# Connector.net
KiCad netlist of a schematic drawn in Altium Designer
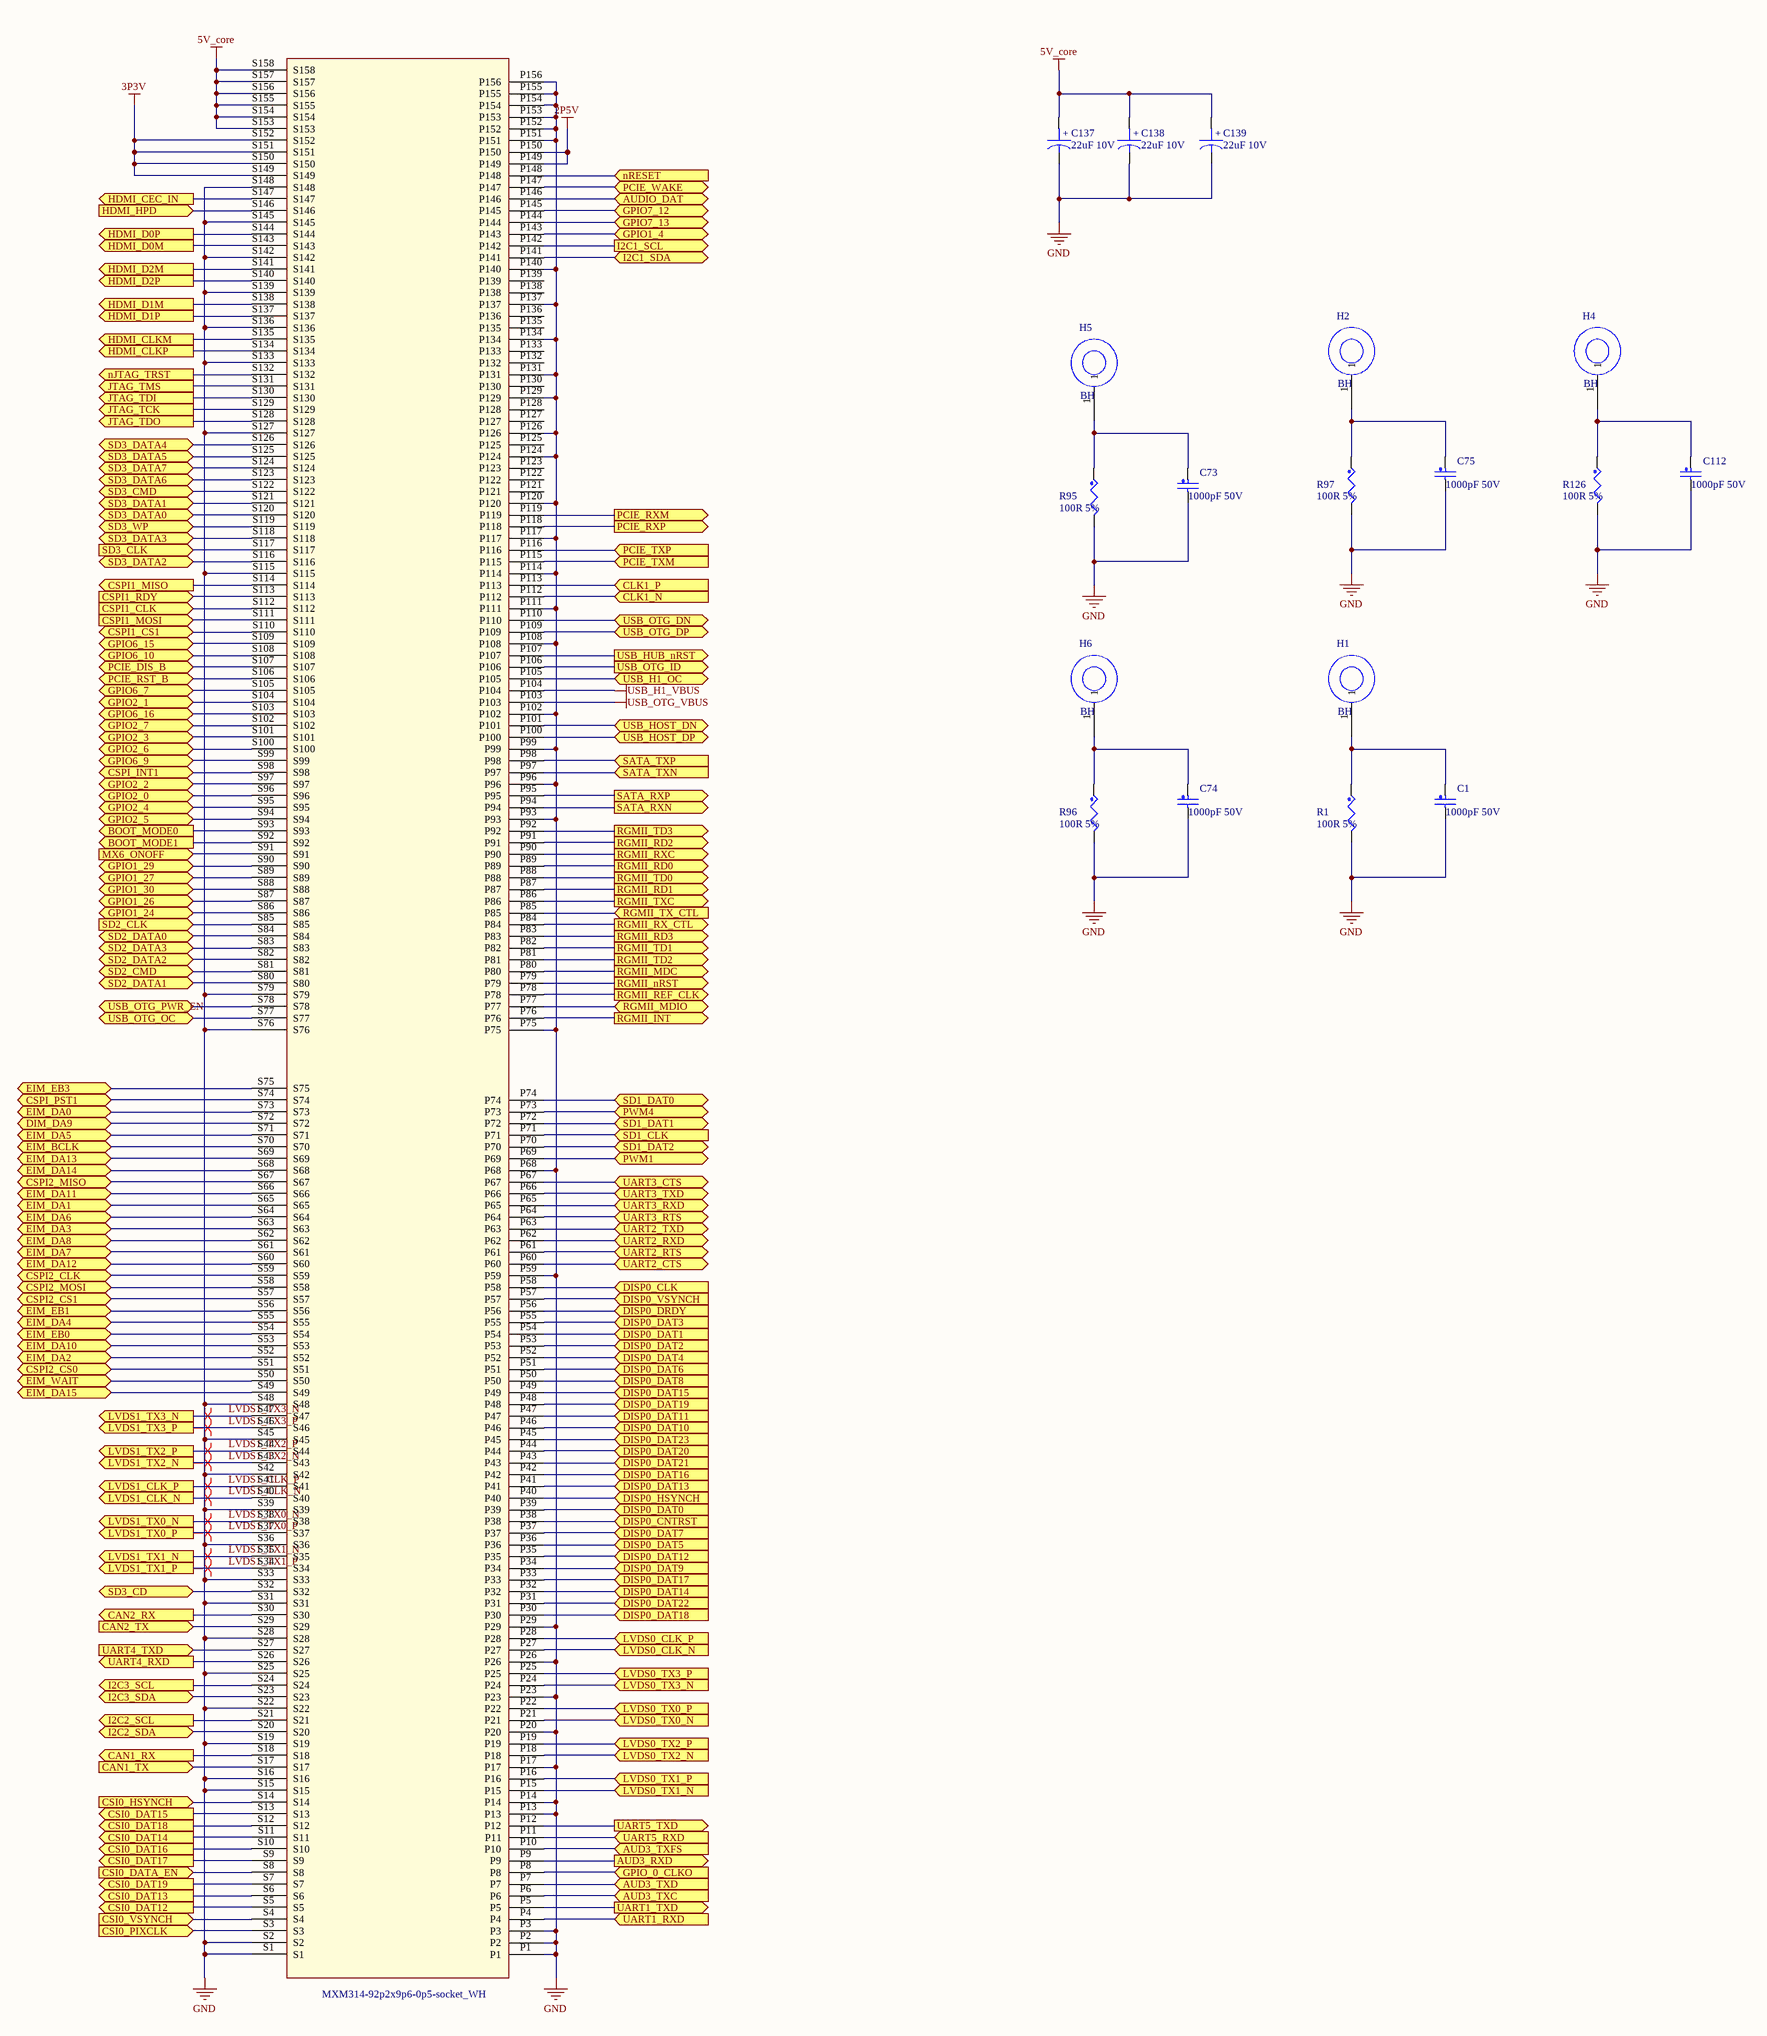
[diagram p0: Connector.SchDoc]

(export (version "E")
  (design (tool "Eeschema 10.0.6"))
  (components
    (comp (ref "C1")
      (value "1000pF 50V")
      (footprint "SC0603")
      (libsource (lib "MY-I.MX6-SCH_Library") (part "CAP_NP"))
    )
    (comp (ref "C73")
      (value "1000pF 50V")
      (footprint "SC0603")
      (libsource (lib "MY-I.MX6-SCH_Library") (part "CAP_NP"))
    )
    (comp (ref "C74")
      (value "1000pF 50V")
      (footprint "SC0603")
      (libsource (lib "MY-I.MX6-SCH_Library") (part "CAP_NP"))
    )
    (comp (ref "C75")
      (value "1000pF 50V")
      (footprint "SC0603")
      (libsource (lib "MY-I.MX6-SCH_Library") (part "CAP_NP"))
    )
    (comp (ref "C112")
      (value "1000pF 50V")
      (footprint "SC0603")
      (libsource (lib "MY-I.MX6-SCH_Library") (part "CAP_NP"))
    )
    (comp (ref "C137")
      (value "22uF 10V")
      (footprint "SC0805")
      (libsource (lib "MY-I.MX6-SCH_Library") (part "CAP POL"))
    )
    (comp (ref "C138")
      (value "22uF 10V")
      (footprint "SC0805")
      (libsource (lib "MY-I.MX6-SCH_Library") (part "CAP POL"))
    )
    (comp (ref "C139")
      (value "22uF 10V")
      (footprint "SC0805")
      (libsource (lib "MY-I.MX6-SCH_Library") (part "CAP POL"))
    )
    (comp (ref "H1") (value "BH") (footprint "H30") (libsource (lib "MY-I.MX6-SCH_Library") (part "BH")))
    (comp (ref "H2") (value "BH") (footprint "H30") (libsource (lib "MY-I.MX6-SCH_Library") (part "BH")))
    (comp (ref "H4") (value "BH") (footprint "H30") (libsource (lib "MY-I.MX6-SCH_Library") (part "BH")))
    (comp (ref "H5") (value "BH") (footprint "H30") (libsource (lib "MY-I.MX6-SCH_Library") (part "BH")))
    (comp (ref "H6") (value "BH") (footprint "H30") (libsource (lib "MY-I.MX6-SCH_Library") (part "BH")))
    (comp (ref "MXM314-92p2x9p6-0p5-socket_WH")
      (value "MXM314-92p2x9p6-0p5-socket_WH")
      (footprint "MXM314-92P2X9P6-0P5-SOCKET_WH")
      (libsource (lib "MY-I.MX6-SCH_Library") (part "MXM314"))
    )
    (comp (ref "R1")
      (value "100R 5%")
      (footprint "SR0603")
      (libsource (lib "MY-I.MX6-SCH_Library") (part "RES"))
    )
    (comp (ref "R95")
      (value "100R 5%")
      (footprint "SR0603")
      (libsource (lib "MY-I.MX6-SCH_Library") (part "RES"))
    )
    (comp (ref "R96")
      (value "100R 5%")
      (footprint "SR0603")
      (libsource (lib "MY-I.MX6-SCH_Library") (part "RES"))
    )
    (comp (ref "R97")
      (value "100R 5%")
      (footprint "SR0603")
      (libsource (lib "MY-I.MX6-SCH_Library") (part "RES"))
    )
    (comp (ref "R126")
      (value "100R 5%")
      (footprint "SR0603")
      (libsource (lib "MY-I.MX6-SCH_Library") (part "RES"))
    )
  )
  (nets
    (net (code "1") (name "/AUD3_RXD") (class "Default")
      (node (ref "MXM314-92p2x9p6-0p5-socket_WH") (pin "P9") (pinfunction "P9_P9") (pintype "passive"))
    )
    (net (code "2") (name "/AUD3_TXC") (class "Default")
      (node (ref "MXM314-92p2x9p6-0p5-socket_WH") (pin "P6") (pinfunction "P6_P6") (pintype "passive"))
    )
    (net (code "3") (name "/AUD3_TXD") (class "Default")
      (node (ref "MXM314-92p2x9p6-0p5-socket_WH") (pin "P7") (pinfunction "P7_P7") (pintype "passive"))
    )
    (net (code "4") (name "/AUD3_TXFS") (class "Default")
      (node (ref "MXM314-92p2x9p6-0p5-socket_WH") (pin "P10") (pinfunction "P10_P10") (pintype "passive"))
    )
    (net (code "5") (name "/AUDIO_DAT") (class "Default")
      (node (ref "MXM314-92p2x9p6-0p5-socket_WH") (pin "P146") (pinfunction "P146_P146") (pintype "passive"))
    )
    (net (code "6") (name "/BOOT_MODE0") (class "Default")
      (node (ref "MXM314-92p2x9p6-0p5-socket_WH") (pin "S93") (pinfunction "S93_S93") (pintype "passive"))
    )
    (net (code "7") (name "/BOOT_MODE1") (class "Default")
      (node (ref "MXM314-92p2x9p6-0p5-socket_WH") (pin "S92") (pinfunction "S92_S92") (pintype "passive"))
    )
    (net (code "8") (name "/CAN1_RX") (class "Default")
      (node (ref "MXM314-92p2x9p6-0p5-socket_WH") (pin "S18") (pinfunction "S18_S18") (pintype "passive"))
    )
    (net (code "9") (name "/CAN1_TX") (class "Default")
      (node (ref "MXM314-92p2x9p6-0p5-socket_WH") (pin "S17") (pinfunction "S17_S17") (pintype "passive"))
    )
    (net (code "10") (name "/CAN2_RX") (class "Default")
      (node (ref "MXM314-92p2x9p6-0p5-socket_WH") (pin "S30") (pinfunction "S30_S30") (pintype "passive"))
    )
    (net (code "11") (name "/CAN2_TX") (class "Default")
      (node (ref "MXM314-92p2x9p6-0p5-socket_WH") (pin "S29") (pinfunction "S29_S29") (pintype "passive"))
    )
    (net (code "12") (name "/CLK1_N") (class "Default")
      (node (ref "MXM314-92p2x9p6-0p5-socket_WH") (pin "P112") (pinfunction "P112_P112") (pintype "passive"))
    )
    (net (code "13") (name "/CLK1_P") (class "Default")
      (node (ref "MXM314-92p2x9p6-0p5-socket_WH") (pin "P113") (pinfunction "P113_P113") (pintype "passive"))
    )
    (net (code "14") (name "/CSI0_DAT12") (class "Default")
      (node (ref "MXM314-92p2x9p6-0p5-socket_WH") (pin "S5") (pinfunction "S5_S5") (pintype "passive"))
    )
    (net (code "15") (name "/CSI0_DAT13") (class "Default")
      (node (ref "MXM314-92p2x9p6-0p5-socket_WH") (pin "S6") (pinfunction "S6_S6") (pintype "passive"))
    )
    (net (code "16") (name "/CSI0_DAT14") (class "Default")
      (node (ref "MXM314-92p2x9p6-0p5-socket_WH") (pin "S11") (pinfunction "S11_S11") (pintype "passive"))
    )
    (net (code "17") (name "/CSI0_DAT15") (class "Default")
      (node (ref "MXM314-92p2x9p6-0p5-socket_WH") (pin "S13") (pinfunction "S13_S13") (pintype "passive"))
    )
    (net (code "18") (name "/CSI0_DAT16") (class "Default")
      (node (ref "MXM314-92p2x9p6-0p5-socket_WH") (pin "S10") (pinfunction "S10_S10") (pintype "passive"))
    )
    (net (code "19") (name "/CSI0_DAT17") (class "Default")
      (node (ref "MXM314-92p2x9p6-0p5-socket_WH") (pin "S9") (pinfunction "S9_S9") (pintype "passive"))
    )
    (net (code "20") (name "/CSI0_DAT18") (class "Default")
      (node (ref "MXM314-92p2x9p6-0p5-socket_WH") (pin "S12") (pinfunction "S12_S12") (pintype "passive"))
    )
    (net (code "21") (name "/CSI0_DAT19") (class "Default")
      (node (ref "MXM314-92p2x9p6-0p5-socket_WH") (pin "S7") (pinfunction "S7_S7") (pintype "passive"))
    )
    (net (code "22") (name "/CSI0_DATA_EN") (class "Default")
      (node (ref "MXM314-92p2x9p6-0p5-socket_WH") (pin "S8") (pinfunction "S8_S8") (pintype "passive"))
    )
    (net (code "23") (name "/CSI0_HSYNCH") (class "Default")
      (node (ref "MXM314-92p2x9p6-0p5-socket_WH") (pin "S14") (pinfunction "S14_S14") (pintype "passive"))
    )
    (net (code "24") (name "/CSI0_PIXCLK") (class "Default")
      (node (ref "MXM314-92p2x9p6-0p5-socket_WH") (pin "S3") (pinfunction "S3_S3") (pintype "passive"))
    )
    (net (code "25") (name "/CSI0_VSYNCH") (class "Default")
      (node (ref "MXM314-92p2x9p6-0p5-socket_WH") (pin "S4") (pinfunction "S4_S4") (pintype "passive"))
    )
    (net (code "26") (name "/CSPI1_CLK") (class "Default")
      (node (ref "MXM314-92p2x9p6-0p5-socket_WH") (pin "S112") (pinfunction "S112_S112") (pintype "passive"))
    )
    (net (code "27") (name "/CSPI1_CS1") (class "Default")
      (node (ref "MXM314-92p2x9p6-0p5-socket_WH") (pin "S110") (pinfunction "S110_S110") (pintype "passive"))
    )
    (net (code "28") (name "/CSPI1_MISO") (class "Default")
      (node (ref "MXM314-92p2x9p6-0p5-socket_WH") (pin "S114") (pinfunction "S114_S114") (pintype "passive"))
    )
    (net (code "29") (name "/CSPI1_MOSI") (class "Default")
      (node (ref "MXM314-92p2x9p6-0p5-socket_WH") (pin "S111") (pinfunction "S111_S111") (pintype "passive"))
    )
    (net (code "30") (name "/CSPI1_RDY") (class "Default")
      (node (ref "MXM314-92p2x9p6-0p5-socket_WH") (pin "S113") (pinfunction "S113_S113") (pintype "passive"))
    )
    (net (code "31") (name "/CSPI2_CLK") (class "Default")
      (node (ref "MXM314-92p2x9p6-0p5-socket_WH") (pin "S59") (pinfunction "S59_S59") (pintype "passive"))
    )
    (net (code "32") (name "/CSPI2_CS0") (class "Default")
      (node (ref "MXM314-92p2x9p6-0p5-socket_WH") (pin "S51") (pinfunction "S51_S51") (pintype "passive"))
    )
    (net (code "33") (name "/CSPI2_CS1") (class "Default")
      (node (ref "MXM314-92p2x9p6-0p5-socket_WH") (pin "S57") (pinfunction "S57_S57") (pintype "passive"))
    )
    (net (code "34") (name "/CSPI2_MISO") (class "Default")
      (node (ref "MXM314-92p2x9p6-0p5-socket_WH") (pin "S67") (pinfunction "S67_S67") (pintype "passive"))
    )
    (net (code "35") (name "/CSPI2_MOSI") (class "Default")
      (node (ref "MXM314-92p2x9p6-0p5-socket_WH") (pin "S58") (pinfunction "S58_S58") (pintype "passive"))
    )
    (net (code "36") (name "/CSPI_INT1") (class "Default")
      (node (ref "MXM314-92p2x9p6-0p5-socket_WH") (pin "S98") (pinfunction "S98_S98") (pintype "passive"))
    )
    (net (code "37") (name "/CSPI_PST1") (class "Default")
      (node (ref "MXM314-92p2x9p6-0p5-socket_WH") (pin "S74") (pinfunction "S74_S74") (pintype "passive"))
    )
    (net (code "38") (name "/DIM_DA9") (class "Default")
      (node (ref "MXM314-92p2x9p6-0p5-socket_WH") (pin "S72") (pinfunction "S72_S72") (pintype "passive"))
    )
    (net (code "39") (name "/DISP0_CLK") (class "Default")
      (node (ref "MXM314-92p2x9p6-0p5-socket_WH") (pin "P58") (pinfunction "P58_P58") (pintype "passive"))
    )
    (net (code "40") (name "/DISP0_CNTRST") (class "Default")
      (node (ref "MXM314-92p2x9p6-0p5-socket_WH") (pin "P38") (pinfunction "P38_P38") (pintype "passive"))
    )
    (net (code "41") (name "/DISP0_DAT0") (class "Default")
      (node (ref "MXM314-92p2x9p6-0p5-socket_WH") (pin "P39") (pinfunction "P39_P39") (pintype "passive"))
    )
    (net (code "42") (name "/DISP0_DAT1") (class "Default")
      (node (ref "MXM314-92p2x9p6-0p5-socket_WH") (pin "P54") (pinfunction "P54_P54") (pintype "passive"))
    )
    (net (code "43") (name "/DISP0_DAT2") (class "Default")
      (node (ref "MXM314-92p2x9p6-0p5-socket_WH") (pin "P53") (pinfunction "P53_P53") (pintype "passive"))
    )
    (net (code "44") (name "/DISP0_DAT3") (class "Default")
      (node (ref "MXM314-92p2x9p6-0p5-socket_WH") (pin "P55") (pinfunction "P55_P55") (pintype "passive"))
    )
    (net (code "45") (name "/DISP0_DAT4") (class "Default")
      (node (ref "MXM314-92p2x9p6-0p5-socket_WH") (pin "P52") (pinfunction "P52_P52") (pintype "passive"))
    )
    (net (code "46") (name "/DISP0_DAT5") (class "Default")
      (node (ref "MXM314-92p2x9p6-0p5-socket_WH") (pin "P36") (pinfunction "P36_P36") (pintype "passive"))
    )
    (net (code "47") (name "/DISP0_DAT6") (class "Default")
      (node (ref "MXM314-92p2x9p6-0p5-socket_WH") (pin "P51") (pinfunction "P51_P51") (pintype "passive"))
    )
    (net (code "48") (name "/DISP0_DAT7") (class "Default")
      (node (ref "MXM314-92p2x9p6-0p5-socket_WH") (pin "P37") (pinfunction "P37_P37") (pintype "passive"))
    )
    (net (code "49") (name "/DISP0_DAT8") (class "Default")
      (node (ref "MXM314-92p2x9p6-0p5-socket_WH") (pin "P50") (pinfunction "P50_P50") (pintype "passive"))
    )
    (net (code "50") (name "/DISP0_DAT9") (class "Default")
      (node (ref "MXM314-92p2x9p6-0p5-socket_WH") (pin "P34") (pinfunction "P34_P34") (pintype "passive"))
    )
    (net (code "51") (name "/DISP0_DAT10") (class "Default")
      (node (ref "MXM314-92p2x9p6-0p5-socket_WH") (pin "P46") (pinfunction "P46_P46") (pintype "passive"))
    )
    (net (code "52") (name "/DISP0_DAT11") (class "Default")
      (node (ref "MXM314-92p2x9p6-0p5-socket_WH") (pin "P47") (pinfunction "P47_P47") (pintype "passive"))
    )
    (net (code "53") (name "/DISP0_DAT12") (class "Default")
      (node (ref "MXM314-92p2x9p6-0p5-socket_WH") (pin "P35") (pinfunction "P35_P35") (pintype "passive"))
    )
    (net (code "54") (name "/DISP0_DAT13") (class "Default")
      (node (ref "MXM314-92p2x9p6-0p5-socket_WH") (pin "P41") (pinfunction "P41_P41") (pintype "passive"))
    )
    (net (code "55") (name "/DISP0_DAT14") (class "Default")
      (node (ref "MXM314-92p2x9p6-0p5-socket_WH") (pin "P32") (pinfunction "P32_P32") (pintype "passive"))
    )
    (net (code "56") (name "/DISP0_DAT15") (class "Default")
      (node (ref "MXM314-92p2x9p6-0p5-socket_WH") (pin "P49") (pinfunction "P49_P49") (pintype "passive"))
    )
    (net (code "57") (name "/DISP0_DAT16") (class "Default")
      (node (ref "MXM314-92p2x9p6-0p5-socket_WH") (pin "P42") (pinfunction "P42_P42") (pintype "passive"))
    )
    (net (code "58") (name "/DISP0_DAT17") (class "Default")
      (node (ref "MXM314-92p2x9p6-0p5-socket_WH") (pin "P33") (pinfunction "P33_P33") (pintype "passive"))
    )
    (net (code "59") (name "/DISP0_DAT18") (class "Default")
      (node (ref "MXM314-92p2x9p6-0p5-socket_WH") (pin "P30") (pinfunction "P30_P30") (pintype "passive"))
    )
    (net (code "60") (name "/DISP0_DAT19") (class "Default")
      (node (ref "MXM314-92p2x9p6-0p5-socket_WH") (pin "P48") (pinfunction "P48_P48") (pintype "passive"))
    )
    (net (code "61") (name "/DISP0_DAT20") (class "Default")
      (node (ref "MXM314-92p2x9p6-0p5-socket_WH") (pin "P44") (pinfunction "P44_P44") (pintype "passive"))
    )
    (net (code "62") (name "/DISP0_DAT21") (class "Default")
      (node (ref "MXM314-92p2x9p6-0p5-socket_WH") (pin "P43") (pinfunction "P43_P43") (pintype "passive"))
    )
    (net (code "63") (name "/DISP0_DAT22") (class "Default")
      (node (ref "MXM314-92p2x9p6-0p5-socket_WH") (pin "P31") (pinfunction "P31_P31") (pintype "passive"))
    )
    (net (code "64") (name "/DISP0_DAT23") (class "Default")
      (node (ref "MXM314-92p2x9p6-0p5-socket_WH") (pin "P45") (pinfunction "P45_P45") (pintype "passive"))
    )
    (net (code "65") (name "/DISP0_DRDY") (class "Default")
      (node (ref "MXM314-92p2x9p6-0p5-socket_WH") (pin "P56") (pinfunction "P56_P56") (pintype "passive"))
    )
    (net (code "66") (name "/DISP0_HSYNCH") (class "Default")
      (node (ref "MXM314-92p2x9p6-0p5-socket_WH") (pin "P40") (pinfunction "P40_P40") (pintype "passive"))
    )
    (net (code "67") (name "/DISP0_VSYNCH") (class "Default")
      (node (ref "MXM314-92p2x9p6-0p5-socket_WH") (pin "P57") (pinfunction "P57_P57") (pintype "passive"))
    )
    (net (code "68") (name "/EIM_BCLK") (class "Default")
      (node (ref "MXM314-92p2x9p6-0p5-socket_WH") (pin "S70") (pinfunction "S70_S70") (pintype "passive"))
    )
    (net (code "69") (name "/EIM_DA0") (class "Default")
      (node (ref "MXM314-92p2x9p6-0p5-socket_WH") (pin "S73") (pinfunction "S73_S73") (pintype "passive"))
    )
    (net (code "70") (name "/EIM_DA1") (class "Default")
      (node (ref "MXM314-92p2x9p6-0p5-socket_WH") (pin "S65") (pinfunction "S65_S65") (pintype "passive"))
    )
    (net (code "71") (name "/EIM_DA2") (class "Default")
      (node (ref "MXM314-92p2x9p6-0p5-socket_WH") (pin "S52") (pinfunction "S52_S52") (pintype "passive"))
    )
    (net (code "72") (name "/EIM_DA3") (class "Default")
      (node (ref "MXM314-92p2x9p6-0p5-socket_WH") (pin "S63") (pinfunction "S63_S63") (pintype "passive"))
    )
    (net (code "73") (name "/EIM_DA4") (class "Default")
      (node (ref "MXM314-92p2x9p6-0p5-socket_WH") (pin "S55") (pinfunction "S55_S55") (pintype "passive"))
    )
    (net (code "74") (name "/EIM_DA5") (class "Default")
      (node (ref "MXM314-92p2x9p6-0p5-socket_WH") (pin "S71") (pinfunction "S71_S71") (pintype "passive"))
    )
    (net (code "75") (name "/EIM_DA6") (class "Default")
      (node (ref "MXM314-92p2x9p6-0p5-socket_WH") (pin "S64") (pinfunction "S64_S64") (pintype "passive"))
    )
    (net (code "76") (name "/EIM_DA7") (class "Default")
      (node (ref "MXM314-92p2x9p6-0p5-socket_WH") (pin "S61") (pinfunction "S61_S61") (pintype "passive"))
    )
    (net (code "77") (name "/EIM_DA8") (class "Default")
      (node (ref "MXM314-92p2x9p6-0p5-socket_WH") (pin "S62") (pinfunction "S62_S62") (pintype "passive"))
    )
    (net (code "78") (name "/EIM_DA10") (class "Default")
      (node (ref "MXM314-92p2x9p6-0p5-socket_WH") (pin "S53") (pinfunction "S53_S53") (pintype "passive"))
    )
    (net (code "79") (name "/EIM_DA11") (class "Default")
      (node (ref "MXM314-92p2x9p6-0p5-socket_WH") (pin "S66") (pinfunction "S66_S66") (pintype "passive"))
    )
    (net (code "80") (name "/EIM_DA12") (class "Default")
      (node (ref "MXM314-92p2x9p6-0p5-socket_WH") (pin "S60") (pinfunction "S60_S60") (pintype "passive"))
    )
    (net (code "81") (name "/EIM_DA13") (class "Default")
      (node (ref "MXM314-92p2x9p6-0p5-socket_WH") (pin "S69") (pinfunction "S69_S69") (pintype "passive"))
    )
    (net (code "82") (name "/EIM_DA14") (class "Default")
      (node (ref "MXM314-92p2x9p6-0p5-socket_WH") (pin "S68") (pinfunction "S68_S68") (pintype "passive"))
    )
    (net (code "83") (name "/EIM_DA15") (class "Default")
      (node (ref "MXM314-92p2x9p6-0p5-socket_WH") (pin "S49") (pinfunction "S49_S49") (pintype "passive"))
    )
    (net (code "84") (name "/EIM_EB0") (class "Default")
      (node (ref "MXM314-92p2x9p6-0p5-socket_WH") (pin "S54") (pinfunction "S54_S54") (pintype "passive"))
    )
    (net (code "85") (name "/EIM_EB1") (class "Default")
      (node (ref "MXM314-92p2x9p6-0p5-socket_WH") (pin "S56") (pinfunction "S56_S56") (pintype "passive"))
    )
    (net (code "86") (name "/EIM_EB3") (class "Default")
      (node (ref "MXM314-92p2x9p6-0p5-socket_WH") (pin "S75") (pinfunction "S75_S75") (pintype "passive"))
    )
    (net (code "87") (name "/EIM_WAIT") (class "Default")
      (node (ref "MXM314-92p2x9p6-0p5-socket_WH") (pin "S50") (pinfunction "S50_S50") (pintype "passive"))
    )
    (net (code "88") (name "/GPIO1_4") (class "Default")
      (node (ref "MXM314-92p2x9p6-0p5-socket_WH") (pin "P143") (pinfunction "P143_P143") (pintype "passive"))
    )
    (net (code "89") (name "/GPIO1_24") (class "Default")
      (node (ref "MXM314-92p2x9p6-0p5-socket_WH") (pin "S86") (pinfunction "S86_S86") (pintype "passive"))
    )
    (net (code "90") (name "/GPIO1_26") (class "Default")
      (node (ref "MXM314-92p2x9p6-0p5-socket_WH") (pin "S87") (pinfunction "S87_S87") (pintype "passive"))
    )
    (net (code "91") (name "/GPIO1_27") (class "Default")
      (node (ref "MXM314-92p2x9p6-0p5-socket_WH") (pin "S89") (pinfunction "S89_S89") (pintype "passive"))
    )
    (net (code "92") (name "/GPIO1_29") (class "Default")
      (node (ref "MXM314-92p2x9p6-0p5-socket_WH") (pin "S90") (pinfunction "S90_S90") (pintype "passive"))
    )
    (net (code "93") (name "/GPIO1_30") (class "Default")
      (node (ref "MXM314-92p2x9p6-0p5-socket_WH") (pin "S88") (pinfunction "S88_S88") (pintype "passive"))
    )
    (net (code "94") (name "/GPIO2_0") (class "Default")
      (node (ref "MXM314-92p2x9p6-0p5-socket_WH") (pin "S96") (pinfunction "S96_S96") (pintype "passive"))
    )
    (net (code "95") (name "/GPIO2_1") (class "Default")
      (node (ref "MXM314-92p2x9p6-0p5-socket_WH") (pin "S104") (pinfunction "S104_S104") (pintype "passive"))
    )
    (net (code "96") (name "/GPIO2_2") (class "Default")
      (node (ref "MXM314-92p2x9p6-0p5-socket_WH") (pin "S97") (pinfunction "S97_S97") (pintype "passive"))
    )
    (net (code "97") (name "/GPIO2_3") (class "Default")
      (node (ref "MXM314-92p2x9p6-0p5-socket_WH") (pin "S101") (pinfunction "S101_S101") (pintype "passive"))
    )
    (net (code "98") (name "/GPIO2_4") (class "Default")
      (node (ref "MXM314-92p2x9p6-0p5-socket_WH") (pin "S95") (pinfunction "S95_S95") (pintype "passive"))
    )
    (net (code "99") (name "/GPIO2_5") (class "Default")
      (node (ref "MXM314-92p2x9p6-0p5-socket_WH") (pin "S94") (pinfunction "S94_S94") (pintype "passive"))
    )
    (net (code "100") (name "/GPIO2_6") (class "Default")
      (node (ref "MXM314-92p2x9p6-0p5-socket_WH") (pin "S100") (pinfunction "S100_S100") (pintype "passive"))
    )
    (net (code "101") (name "/GPIO2_7") (class "Default")
      (node (ref "MXM314-92p2x9p6-0p5-socket_WH") (pin "S102") (pinfunction "S102_S102") (pintype "passive"))
    )
    (net (code "102") (name "/GPIO6_7") (class "Default")
      (node (ref "MXM314-92p2x9p6-0p5-socket_WH") (pin "S105") (pinfunction "S105_S105") (pintype "passive"))
    )
    (net (code "103") (name "/GPIO6_9") (class "Default")
      (node (ref "MXM314-92p2x9p6-0p5-socket_WH") (pin "S99") (pinfunction "S99_S99") (pintype "passive"))
    )
    (net (code "104") (name "/GPIO6_10") (class "Default")
      (node (ref "MXM314-92p2x9p6-0p5-socket_WH") (pin "S108") (pinfunction "S108_S108") (pintype "passive"))
    )
    (net (code "105") (name "/GPIO6_15") (class "Default")
      (node (ref "MXM314-92p2x9p6-0p5-socket_WH") (pin "S109") (pinfunction "S109_S109") (pintype "passive"))
    )
    (net (code "106") (name "/GPIO6_16") (class "Default")
      (node (ref "MXM314-92p2x9p6-0p5-socket_WH") (pin "S103") (pinfunction "S103_S103") (pintype "passive"))
    )
    (net (code "107") (name "/GPIO7_12") (class "Default")
      (node (ref "MXM314-92p2x9p6-0p5-socket_WH") (pin "P145") (pinfunction "P145_P145") (pintype "passive"))
    )
    (net (code "108") (name "/GPIO7_13") (class "Default")
      (node (ref "MXM314-92p2x9p6-0p5-socket_WH") (pin "P144") (pinfunction "P144_P144") (pintype "passive"))
    )
    (net (code "109") (name "/GPIO_0_CLKO") (class "Default")
      (node (ref "MXM314-92p2x9p6-0p5-socket_WH") (pin "P8") (pinfunction "P8_P8") (pintype "passive"))
    )
    (net (code "110") (name "/HDMI_CEC_IN") (class "Default")
      (node (ref "MXM314-92p2x9p6-0p5-socket_WH") (pin "S147") (pinfunction "S147_S147") (pintype "passive"))
    )
    (net (code "111") (name "/HDMI_CLKM") (class "Default")
      (node (ref "MXM314-92p2x9p6-0p5-socket_WH") (pin "S135") (pinfunction "S135_S135") (pintype "passive"))
    )
    (net (code "112") (name "/HDMI_CLKP") (class "Default")
      (node (ref "MXM314-92p2x9p6-0p5-socket_WH") (pin "S134") (pinfunction "S134_S134") (pintype "passive"))
    )
    (net (code "113") (name "/HDMI_D0M") (class "Default")
      (node (ref "MXM314-92p2x9p6-0p5-socket_WH") (pin "S143") (pinfunction "S143_S143") (pintype "passive"))
    )
    (net (code "114") (name "/HDMI_D0P") (class "Default")
      (node (ref "MXM314-92p2x9p6-0p5-socket_WH") (pin "S144") (pinfunction "S144_S144") (pintype "passive"))
    )
    (net (code "115") (name "/HDMI_D1M") (class "Default")
      (node (ref "MXM314-92p2x9p6-0p5-socket_WH") (pin "S138") (pinfunction "S138_S138") (pintype "passive"))
    )
    (net (code "116") (name "/HDMI_D1P") (class "Default")
      (node (ref "MXM314-92p2x9p6-0p5-socket_WH") (pin "S137") (pinfunction "S137_S137") (pintype "passive"))
    )
    (net (code "117") (name "/HDMI_D2M") (class "Default")
      (node (ref "MXM314-92p2x9p6-0p5-socket_WH") (pin "S141") (pinfunction "S141_S141") (pintype "passive"))
    )
    (net (code "118") (name "/HDMI_D2P") (class "Default")
      (node (ref "MXM314-92p2x9p6-0p5-socket_WH") (pin "S140") (pinfunction "S140_S140") (pintype "passive"))
    )
    (net (code "119") (name "/HDMI_HPD") (class "Default")
      (node (ref "MXM314-92p2x9p6-0p5-socket_WH") (pin "S146") (pinfunction "S146_S146") (pintype "passive"))
    )
    (net (code "120") (name "/I2C1_SCL") (class "Default")
      (node (ref "MXM314-92p2x9p6-0p5-socket_WH") (pin "P142") (pinfunction "P142_P142") (pintype "passive"))
    )
    (net (code "121") (name "/I2C1_SDA") (class "Default")
      (node (ref "MXM314-92p2x9p6-0p5-socket_WH") (pin "P141") (pinfunction "P141_P141") (pintype "passive"))
    )
    (net (code "122") (name "/I2C2_SCL") (class "Default")
      (node (ref "MXM314-92p2x9p6-0p5-socket_WH") (pin "S21") (pinfunction "S21_S21") (pintype "passive"))
    )
    (net (code "123") (name "/I2C2_SDA") (class "Default")
      (node (ref "MXM314-92p2x9p6-0p5-socket_WH") (pin "S20") (pinfunction "S20_S20") (pintype "passive"))
    )
    (net (code "124") (name "/I2C3_SCL") (class "Default")
      (node (ref "MXM314-92p2x9p6-0p5-socket_WH") (pin "S24") (pinfunction "S24_S24") (pintype "passive"))
    )
    (net (code "125") (name "/I2C3_SDA") (class "Default")
      (node (ref "MXM314-92p2x9p6-0p5-socket_WH") (pin "S23") (pinfunction "S23_S23") (pintype "passive"))
    )
    (net (code "126") (name "/JTAG_TCK") (class "Default")
      (node (ref "MXM314-92p2x9p6-0p5-socket_WH") (pin "S129") (pinfunction "S129_S129") (pintype "passive"))
    )
    (net (code "127") (name "/JTAG_TDI") (class "Default")
      (node (ref "MXM314-92p2x9p6-0p5-socket_WH") (pin "S130") (pinfunction "S130_S130") (pintype "passive"))
    )
    (net (code "128") (name "/JTAG_TDO") (class "Default")
      (node (ref "MXM314-92p2x9p6-0p5-socket_WH") (pin "S128") (pinfunction "S128_S128") (pintype "passive"))
    )
    (net (code "129") (name "/JTAG_TMS") (class "Default")
      (node (ref "MXM314-92p2x9p6-0p5-socket_WH") (pin "S131") (pinfunction "S131_S131") (pintype "passive"))
    )
    (net (code "130") (name "/LVDS0_CLK_N") (class "Default")
      (node (ref "MXM314-92p2x9p6-0p5-socket_WH") (pin "P27") (pinfunction "P27_P27") (pintype "passive"))
    )
    (net (code "131") (name "/LVDS0_CLK_P") (class "Default")
      (node (ref "MXM314-92p2x9p6-0p5-socket_WH") (pin "P28") (pinfunction "P28_P28") (pintype "passive"))
    )
    (net (code "132") (name "/LVDS0_TX0_N") (class "Default")
      (node (ref "MXM314-92p2x9p6-0p5-socket_WH") (pin "P21") (pinfunction "P21_P21") (pintype "passive"))
    )
    (net (code "133") (name "/LVDS0_TX0_P") (class "Default")
      (node (ref "MXM314-92p2x9p6-0p5-socket_WH") (pin "P22") (pinfunction "P22_P22") (pintype "passive"))
    )
    (net (code "134") (name "/LVDS0_TX1_N") (class "Default")
      (node (ref "MXM314-92p2x9p6-0p5-socket_WH") (pin "P15") (pinfunction "P15_P15") (pintype "passive"))
    )
    (net (code "135") (name "/LVDS0_TX1_P") (class "Default")
      (node (ref "MXM314-92p2x9p6-0p5-socket_WH") (pin "P16") (pinfunction "P16_P16") (pintype "passive"))
    )
    (net (code "136") (name "/LVDS0_TX2_N") (class "Default")
      (node (ref "MXM314-92p2x9p6-0p5-socket_WH") (pin "P18") (pinfunction "P18_P18") (pintype "passive"))
    )
    (net (code "137") (name "/LVDS0_TX2_P") (class "Default")
      (node (ref "MXM314-92p2x9p6-0p5-socket_WH") (pin "P19") (pinfunction "P19_P19") (pintype "passive"))
    )
    (net (code "138") (name "/LVDS0_TX3_N") (class "Default")
      (node (ref "MXM314-92p2x9p6-0p5-socket_WH") (pin "P24") (pinfunction "P24_P24") (pintype "passive"))
    )
    (net (code "139") (name "/LVDS0_TX3_P") (class "Default")
      (node (ref "MXM314-92p2x9p6-0p5-socket_WH") (pin "P25") (pinfunction "P25_P25") (pintype "passive"))
    )
    (net (code "140") (name "/LVDS1_CLK_N") (class "Default")
      (node (ref "MXM314-92p2x9p6-0p5-socket_WH") (pin "S40") (pinfunction "S40_S40") (pintype "passive"))
    )
    (net (code "141") (name "/LVDS1_CLK_P") (class "Default")
      (node (ref "MXM314-92p2x9p6-0p5-socket_WH") (pin "S41") (pinfunction "S41_S41") (pintype "passive"))
    )
    (net (code "142") (name "/LVDS1_TX0_N") (class "Default")
      (node (ref "MXM314-92p2x9p6-0p5-socket_WH") (pin "S38") (pinfunction "S38_S38") (pintype "passive"))
    )
    (net (code "143") (name "/LVDS1_TX0_P") (class "Default")
      (node (ref "MXM314-92p2x9p6-0p5-socket_WH") (pin "S37") (pinfunction "S37_S37") (pintype "passive"))
    )
    (net (code "144") (name "/LVDS1_TX1_N") (class "Default")
      (node (ref "MXM314-92p2x9p6-0p5-socket_WH") (pin "S35") (pinfunction "S35_S35") (pintype "passive"))
    )
    (net (code "145") (name "/LVDS1_TX1_P") (class "Default")
      (node (ref "MXM314-92p2x9p6-0p5-socket_WH") (pin "S34") (pinfunction "S34_S34") (pintype "passive"))
    )
    (net (code "146") (name "/LVDS1_TX2_N") (class "Default")
      (node (ref "MXM314-92p2x9p6-0p5-socket_WH") (pin "S43") (pinfunction "S43_S43") (pintype "passive"))
    )
    (net (code "147") (name "/LVDS1_TX2_P") (class "Default")
      (node (ref "MXM314-92p2x9p6-0p5-socket_WH") (pin "S44") (pinfunction "S44_S44") (pintype "passive"))
    )
    (net (code "148") (name "/LVDS1_TX3_N") (class "Default")
      (node (ref "MXM314-92p2x9p6-0p5-socket_WH") (pin "S47") (pinfunction "S47_S47") (pintype "passive"))
    )
    (net (code "149") (name "/LVDS1_TX3_P") (class "Default")
      (node (ref "MXM314-92p2x9p6-0p5-socket_WH") (pin "S46") (pinfunction "S46_S46") (pintype "passive"))
    )
    (net (code "150") (name "/MX6_ONOFF") (class "Default")
      (node (ref "MXM314-92p2x9p6-0p5-socket_WH") (pin "S91") (pinfunction "S91_S91") (pintype "passive"))
    )
    (net (code "151") (name "/PCIE_DIS_B") (class "Default")
      (node (ref "MXM314-92p2x9p6-0p5-socket_WH") (pin "S107") (pinfunction "S107_S107") (pintype "passive"))
    )
    (net (code "152") (name "/PCIE_RST_B") (class "Default")
      (node (ref "MXM314-92p2x9p6-0p5-socket_WH") (pin "S106") (pinfunction "S106_S106") (pintype "passive"))
    )
    (net (code "153") (name "/PCIE_RXM") (class "Default")
      (node (ref "MXM314-92p2x9p6-0p5-socket_WH") (pin "P119") (pinfunction "P119_P119") (pintype "passive"))
    )
    (net (code "154") (name "/PCIE_RXP") (class "Default")
      (node (ref "MXM314-92p2x9p6-0p5-socket_WH") (pin "P118") (pinfunction "P118_P118") (pintype "passive"))
    )
    (net (code "155") (name "/PCIE_TXM") (class "Default")
      (node (ref "MXM314-92p2x9p6-0p5-socket_WH") (pin "P115") (pinfunction "P115_P115") (pintype "passive"))
    )
    (net (code "156") (name "/PCIE_TXP") (class "Default")
      (node (ref "MXM314-92p2x9p6-0p5-socket_WH") (pin "P116") (pinfunction "P116_P116") (pintype "passive"))
    )
    (net (code "157") (name "/PCIE_WAKE") (class "Default")
      (node (ref "MXM314-92p2x9p6-0p5-socket_WH") (pin "P147") (pinfunction "P147_P147") (pintype "passive"))
    )
    (net (code "158") (name "/PWM1") (class "Default")
      (node (ref "MXM314-92p2x9p6-0p5-socket_WH") (pin "P69") (pinfunction "P69_P69") (pintype "passive"))
    )
    (net (code "159") (name "/PWM4") (class "Default")
      (node (ref "MXM314-92p2x9p6-0p5-socket_WH") (pin "P73") (pinfunction "P73_P73") (pintype "passive"))
    )
    (net (code "160") (name "/RGMII_INT") (class "Default")
      (node (ref "MXM314-92p2x9p6-0p5-socket_WH") (pin "P76") (pinfunction "P76_P76") (pintype "passive"))
    )
    (net (code "161") (name "/RGMII_MDC") (class "Default")
      (node (ref "MXM314-92p2x9p6-0p5-socket_WH") (pin "P80") (pinfunction "P80_P80") (pintype "passive"))
    )
    (net (code "162") (name "/RGMII_MDIO") (class "Default")
      (node (ref "MXM314-92p2x9p6-0p5-socket_WH") (pin "P77") (pinfunction "P77_P77") (pintype "passive"))
    )
    (net (code "163") (name "/RGMII_RD0") (class "Default")
      (node (ref "MXM314-92p2x9p6-0p5-socket_WH") (pin "P89") (pinfunction "P89_P89") (pintype "passive"))
    )
    (net (code "164") (name "/RGMII_RD1") (class "Default")
      (node (ref "MXM314-92p2x9p6-0p5-socket_WH") (pin "P87") (pinfunction "P87_P87") (pintype "passive"))
    )
    (net (code "165") (name "/RGMII_RD2") (class "Default")
      (node (ref "MXM314-92p2x9p6-0p5-socket_WH") (pin "P91") (pinfunction "P91_P91") (pintype "passive"))
    )
    (net (code "166") (name "/RGMII_RD3") (class "Default")
      (node (ref "MXM314-92p2x9p6-0p5-socket_WH") (pin "P83") (pinfunction "P83_P83") (pintype "passive"))
    )
    (net (code "167") (name "/RGMII_REF_CLK") (class "Default")
      (node (ref "MXM314-92p2x9p6-0p5-socket_WH") (pin "P78") (pinfunction "P78_P78") (pintype "passive"))
    )
    (net (code "168") (name "/RGMII_RXC") (class "Default")
      (node (ref "MXM314-92p2x9p6-0p5-socket_WH") (pin "P90") (pinfunction "P90_P90") (pintype "passive"))
    )
    (net (code "169") (name "/RGMII_RX_CTL") (class "Default")
      (node (ref "MXM314-92p2x9p6-0p5-socket_WH") (pin "P84") (pinfunction "P84_P84") (pintype "passive"))
    )
    (net (code "170") (name "/RGMII_TD0") (class "Default")
      (node (ref "MXM314-92p2x9p6-0p5-socket_WH") (pin "P88") (pinfunction "P88_P88") (pintype "passive"))
    )
    (net (code "171") (name "/RGMII_TD1") (class "Default")
      (node (ref "MXM314-92p2x9p6-0p5-socket_WH") (pin "P82") (pinfunction "P82_P82") (pintype "passive"))
    )
    (net (code "172") (name "/RGMII_TD2") (class "Default")
      (node (ref "MXM314-92p2x9p6-0p5-socket_WH") (pin "P81") (pinfunction "P81_P81") (pintype "passive"))
    )
    (net (code "173") (name "/RGMII_TD3") (class "Default")
      (node (ref "MXM314-92p2x9p6-0p5-socket_WH") (pin "P92") (pinfunction "P92_P92") (pintype "passive"))
    )
    (net (code "174") (name "/RGMII_TXC") (class "Default")
      (node (ref "MXM314-92p2x9p6-0p5-socket_WH") (pin "P86") (pinfunction "P86_P86") (pintype "passive"))
    )
    (net (code "175") (name "/RGMII_TX_CTL") (class "Default")
      (node (ref "MXM314-92p2x9p6-0p5-socket_WH") (pin "P85") (pinfunction "P85_P85") (pintype "passive"))
    )
    (net (code "176") (name "/RGMII_nRST") (class "Default")
      (node (ref "MXM314-92p2x9p6-0p5-socket_WH") (pin "P79") (pinfunction "P79_P79") (pintype "passive"))
    )
    (net (code "177") (name "/SATA_RXN") (class "Default")
      (node (ref "MXM314-92p2x9p6-0p5-socket_WH") (pin "P94") (pinfunction "P94_P94") (pintype "passive"))
    )
    (net (code "178") (name "/SATA_RXP") (class "Default")
      (node (ref "MXM314-92p2x9p6-0p5-socket_WH") (pin "P95") (pinfunction "P95_P95") (pintype "passive"))
    )
    (net (code "179") (name "/SATA_TXN") (class "Default")
      (node (ref "MXM314-92p2x9p6-0p5-socket_WH") (pin "P97") (pinfunction "P97_P97") (pintype "passive"))
    )
    (net (code "180") (name "/SATA_TXP") (class "Default")
      (node (ref "MXM314-92p2x9p6-0p5-socket_WH") (pin "P98") (pinfunction "P98_P98") (pintype "passive"))
    )
    (net (code "181") (name "/SD1_CLK") (class "Default")
      (node (ref "MXM314-92p2x9p6-0p5-socket_WH") (pin "P71") (pinfunction "P71_P71") (pintype "passive"))
    )
    (net (code "182") (name "/SD1_DAT0") (class "Default")
      (node (ref "MXM314-92p2x9p6-0p5-socket_WH") (pin "P74") (pinfunction "P74_P74") (pintype "passive"))
    )
    (net (code "183") (name "/SD1_DAT1") (class "Default")
      (node (ref "MXM314-92p2x9p6-0p5-socket_WH") (pin "P72") (pinfunction "P72_P72") (pintype "passive"))
    )
    (net (code "184") (name "/SD1_DAT2") (class "Default")
      (node (ref "MXM314-92p2x9p6-0p5-socket_WH") (pin "P70") (pinfunction "P70_P70") (pintype "passive"))
    )
    (net (code "185") (name "/SD2_CLK") (class "Default")
      (node (ref "MXM314-92p2x9p6-0p5-socket_WH") (pin "S85") (pinfunction "S85_S85") (pintype "passive"))
    )
    (net (code "186") (name "/SD2_CMD") (class "Default")
      (node (ref "MXM314-92p2x9p6-0p5-socket_WH") (pin "S81") (pinfunction "S81_S81") (pintype "passive"))
    )
    (net (code "187") (name "/SD2_DATA0") (class "Default")
      (node (ref "MXM314-92p2x9p6-0p5-socket_WH") (pin "S84") (pinfunction "S84_S84") (pintype "passive"))
    )
    (net (code "188") (name "/SD2_DATA1") (class "Default")
      (node (ref "MXM314-92p2x9p6-0p5-socket_WH") (pin "S80") (pinfunction "S80_S80") (pintype "passive"))
    )
    (net (code "189") (name "/SD2_DATA2") (class "Default")
      (node (ref "MXM314-92p2x9p6-0p5-socket_WH") (pin "S82") (pinfunction "S82_S82") (pintype "passive"))
    )
    (net (code "190") (name "/SD2_DATA3") (class "Default")
      (node (ref "MXM314-92p2x9p6-0p5-socket_WH") (pin "S83") (pinfunction "S83_S83") (pintype "passive"))
    )
    (net (code "191") (name "/SD3_CD") (class "Default")
      (node (ref "MXM314-92p2x9p6-0p5-socket_WH") (pin "S32") (pinfunction "S32_S32") (pintype "passive"))
    )
    (net (code "192") (name "/SD3_CLK") (class "Default")
      (node (ref "MXM314-92p2x9p6-0p5-socket_WH") (pin "S117") (pinfunction "S117_S117") (pintype "passive"))
    )
    (net (code "193") (name "/SD3_CMD") (class "Default")
      (node (ref "MXM314-92p2x9p6-0p5-socket_WH") (pin "S122") (pinfunction "S122_S122") (pintype "passive"))
    )
    (net (code "194") (name "/SD3_DATA0") (class "Default")
      (node (ref "MXM314-92p2x9p6-0p5-socket_WH") (pin "S120") (pinfunction "S120_S120") (pintype "passive"))
    )
    (net (code "195") (name "/SD3_DATA1") (class "Default")
      (node (ref "MXM314-92p2x9p6-0p5-socket_WH") (pin "S121") (pinfunction "S121_S121") (pintype "passive"))
    )
    (net (code "196") (name "/SD3_DATA2") (class "Default")
      (node (ref "MXM314-92p2x9p6-0p5-socket_WH") (pin "S116") (pinfunction "S116_S116") (pintype "passive"))
    )
    (net (code "197") (name "/SD3_DATA3") (class "Default")
      (node (ref "MXM314-92p2x9p6-0p5-socket_WH") (pin "S118") (pinfunction "S118_S118") (pintype "passive"))
    )
    (net (code "198") (name "/SD3_DATA4") (class "Default")
      (node (ref "MXM314-92p2x9p6-0p5-socket_WH") (pin "S126") (pinfunction "S126_S126") (pintype "passive"))
    )
    (net (code "199") (name "/SD3_DATA5") (class "Default")
      (node (ref "MXM314-92p2x9p6-0p5-socket_WH") (pin "S125") (pinfunction "S125_S125") (pintype "passive"))
    )
    (net (code "200") (name "/SD3_DATA6") (class "Default")
      (node (ref "MXM314-92p2x9p6-0p5-socket_WH") (pin "S123") (pinfunction "S123_S123") (pintype "passive"))
    )
    (net (code "201") (name "/SD3_DATA7") (class "Default")
      (node (ref "MXM314-92p2x9p6-0p5-socket_WH") (pin "S124") (pinfunction "S124_S124") (pintype "passive"))
    )
    (net (code "202") (name "/SD3_WP") (class "Default")
      (node (ref "MXM314-92p2x9p6-0p5-socket_WH") (pin "S119") (pinfunction "S119_S119") (pintype "passive"))
    )
    (net (code "203") (name "/UART1_RXD") (class "Default")
      (node (ref "MXM314-92p2x9p6-0p5-socket_WH") (pin "P4") (pinfunction "P4_P4") (pintype "passive"))
    )
    (net (code "204") (name "/UART1_TXD") (class "Default")
      (node (ref "MXM314-92p2x9p6-0p5-socket_WH") (pin "P5") (pinfunction "P5_P5") (pintype "passive"))
    )
    (net (code "205") (name "/UART2_CTS") (class "Default")
      (node (ref "MXM314-92p2x9p6-0p5-socket_WH") (pin "P60") (pinfunction "P60_P60") (pintype "passive"))
    )
    (net (code "206") (name "/UART2_RTS") (class "Default")
      (node (ref "MXM314-92p2x9p6-0p5-socket_WH") (pin "P61") (pinfunction "P61_P61") (pintype "passive"))
    )
    (net (code "207") (name "/UART2_RXD") (class "Default")
      (node (ref "MXM314-92p2x9p6-0p5-socket_WH") (pin "P62") (pinfunction "P62_P62") (pintype "passive"))
    )
    (net (code "208") (name "/UART2_TXD") (class "Default")
      (node (ref "MXM314-92p2x9p6-0p5-socket_WH") (pin "P63") (pinfunction "P63_P63") (pintype "passive"))
    )
    (net (code "209") (name "/UART3_CTS") (class "Default")
      (node (ref "MXM314-92p2x9p6-0p5-socket_WH") (pin "P67") (pinfunction "P67_P67") (pintype "passive"))
    )
    (net (code "210") (name "/UART3_RTS") (class "Default")
      (node (ref "MXM314-92p2x9p6-0p5-socket_WH") (pin "P64") (pinfunction "P64_P64") (pintype "passive"))
    )
    (net (code "211") (name "/UART3_RXD") (class "Default")
      (node (ref "MXM314-92p2x9p6-0p5-socket_WH") (pin "P65") (pinfunction "P65_P65") (pintype "passive"))
    )
    (net (code "212") (name "/UART3_TXD") (class "Default")
      (node (ref "MXM314-92p2x9p6-0p5-socket_WH") (pin "P66") (pinfunction "P66_P66") (pintype "passive"))
    )
    (net (code "213") (name "/UART4_RXD") (class "Default")
      (node (ref "MXM314-92p2x9p6-0p5-socket_WH") (pin "S26") (pinfunction "S26_S26") (pintype "passive"))
    )
    (net (code "214") (name "/UART4_TXD") (class "Default")
      (node (ref "MXM314-92p2x9p6-0p5-socket_WH") (pin "S27") (pinfunction "S27_S27") (pintype "passive"))
    )
    (net (code "215") (name "/UART5_RXD") (class "Default")
      (node (ref "MXM314-92p2x9p6-0p5-socket_WH") (pin "P11") (pinfunction "P11_P11") (pintype "passive"))
    )
    (net (code "216") (name "/UART5_TXD") (class "Default")
      (node (ref "MXM314-92p2x9p6-0p5-socket_WH") (pin "P12") (pinfunction "P12_P12") (pintype "passive"))
    )
    (net (code "217") (name "/USB_H1_OC") (class "Default")
      (node (ref "MXM314-92p2x9p6-0p5-socket_WH") (pin "P105") (pinfunction "P105_P105") (pintype "passive"))
    )
    (net (code "218") (name "/USB_HOST_DN") (class "Default")
      (node (ref "MXM314-92p2x9p6-0p5-socket_WH") (pin "P101") (pinfunction "P101_P101") (pintype "passive"))
    )
    (net (code "219") (name "/USB_HOST_DP") (class "Default")
      (node (ref "MXM314-92p2x9p6-0p5-socket_WH") (pin "P100") (pinfunction "P100_P100") (pintype "passive"))
    )
    (net (code "220") (name "/USB_HUB_nRST") (class "Default")
      (node (ref "MXM314-92p2x9p6-0p5-socket_WH") (pin "P107") (pinfunction "P107_P107") (pintype "passive"))
    )
    (net (code "221") (name "/USB_OTG_DN") (class "Default")
      (node (ref "MXM314-92p2x9p6-0p5-socket_WH") (pin "P110") (pinfunction "P110_P110") (pintype "passive"))
    )
    (net (code "222") (name "/USB_OTG_DP") (class "Default")
      (node (ref "MXM314-92p2x9p6-0p5-socket_WH") (pin "P109") (pinfunction "P109_P109") (pintype "passive"))
    )
    (net (code "223") (name "/USB_OTG_ID") (class "Default")
      (node (ref "MXM314-92p2x9p6-0p5-socket_WH") (pin "P106") (pinfunction "P106_P106") (pintype "passive"))
    )
    (net (code "224") (name "/USB_OTG_OC") (class "Default")
      (node (ref "MXM314-92p2x9p6-0p5-socket_WH") (pin "S77") (pinfunction "S77_S77") (pintype "passive"))
    )
    (net (code "225") (name "/USB_OTG_PWR_EN") (class "Default")
      (node (ref "MXM314-92p2x9p6-0p5-socket_WH") (pin "S78") (pinfunction "S78_S78") (pintype "passive"))
    )
    (net (code "226") (name "/nJTAG_TRST") (class "Default")
      (node (ref "MXM314-92p2x9p6-0p5-socket_WH") (pin "S132") (pinfunction "S132_S132") (pintype "passive"))
    )
    (net (code "227") (name "/nRESET") (class "Default")
      (node (ref "MXM314-92p2x9p6-0p5-socket_WH") (pin "P148") (pinfunction "P148_P148") (pintype "passive"))
    )
    (net (code "228") (name "2P5V") (class "Default")
      (node (ref "MXM314-92p2x9p6-0p5-socket_WH") (pin "P149") (pinfunction "P149_P149") (pintype "passive"))
      (node (ref "MXM314-92p2x9p6-0p5-socket_WH") (pin "P150") (pinfunction "P150_P150") (pintype "passive"))
    )
    (net (code "229") (name "3P3V") (class "Default")
      (node (ref "MXM314-92p2x9p6-0p5-socket_WH") (pin "S149") (pinfunction "S149_S149") (pintype "passive"))
      (node (ref "MXM314-92p2x9p6-0p5-socket_WH") (pin "S150") (pinfunction "S150_S150") (pintype "passive"))
      (node (ref "MXM314-92p2x9p6-0p5-socket_WH") (pin "S151") (pinfunction "S151_S151") (pintype "passive"))
      (node (ref "MXM314-92p2x9p6-0p5-socket_WH") (pin "S152") (pinfunction "S152_S152") (pintype "passive"))
    )
    (net (code "230") (name "5V_core") (class "Default")
      (node (ref "C137") (pin "1") (pinfunction "1_1") (pintype "passive"))
      (node (ref "C138") (pin "1") (pinfunction "1_1") (pintype "passive"))
      (node (ref "C139") (pin "1") (pinfunction "1_1") (pintype "passive"))
      (node (ref "MXM314-92p2x9p6-0p5-socket_WH") (pin "S153") (pinfunction "S153_S153") (pintype "passive"))
      (node (ref "MXM314-92p2x9p6-0p5-socket_WH") (pin "S154") (pinfunction "S154_S154") (pintype "passive"))
      (node (ref "MXM314-92p2x9p6-0p5-socket_WH") (pin "S155") (pinfunction "S155_S155") (pintype "passive"))
      (node (ref "MXM314-92p2x9p6-0p5-socket_WH") (pin "S156") (pinfunction "S156_S156") (pintype "passive"))
      (node (ref "MXM314-92p2x9p6-0p5-socket_WH") (pin "S157") (pinfunction "S157_S157") (pintype "passive"))
      (node (ref "MXM314-92p2x9p6-0p5-socket_WH") (pin "S158") (pinfunction "S158_S158") (pintype "passive"))
    )
    (net (code "231") (name "GND") (class "Default")
      (node (ref "C1") (pin "2") (pinfunction "2_2") (pintype "passive"))
      (node (ref "C112") (pin "2") (pinfunction "2_2") (pintype "passive"))
      (node (ref "C137") (pin "2") (pinfunction "2_2") (pintype "passive"))
      (node (ref "C138") (pin "2") (pinfunction "2_2") (pintype "passive"))
      (node (ref "C139") (pin "2") (pinfunction "2_2") (pintype "passive"))
      (node (ref "C73") (pin "2") (pinfunction "2_2") (pintype "passive"))
      (node (ref "C74") (pin "2") (pinfunction "2_2") (pintype "passive"))
      (node (ref "C75") (pin "2") (pinfunction "2_2") (pintype "passive"))
      (node (ref "MXM314-92p2x9p6-0p5-socket_WH") (pin "P1") (pinfunction "P1_P1") (pintype "passive"))
      (node (ref "MXM314-92p2x9p6-0p5-socket_WH") (pin "P102") (pinfunction "P102_P102") (pintype "passive"))
      (node (ref "MXM314-92p2x9p6-0p5-socket_WH") (pin "P108") (pinfunction "P108_P108") (pintype "passive"))
      (node (ref "MXM314-92p2x9p6-0p5-socket_WH") (pin "P111") (pinfunction "P111_P111") (pintype "passive"))
      (node (ref "MXM314-92p2x9p6-0p5-socket_WH") (pin "P114") (pinfunction "P114_P114") (pintype "passive"))
      (node (ref "MXM314-92p2x9p6-0p5-socket_WH") (pin "P117") (pinfunction "P117_P117") (pintype "passive"))
      (node (ref "MXM314-92p2x9p6-0p5-socket_WH") (pin "P120") (pinfunction "P120_P120") (pintype "passive"))
      (node (ref "MXM314-92p2x9p6-0p5-socket_WH") (pin "P124") (pinfunction "P124_P124") (pintype "passive"))
      (node (ref "MXM314-92p2x9p6-0p5-socket_WH") (pin "P126") (pinfunction "P126_P126") (pintype "passive"))
      (node (ref "MXM314-92p2x9p6-0p5-socket_WH") (pin "P129") (pinfunction "P129_P129") (pintype "passive"))
      (node (ref "MXM314-92p2x9p6-0p5-socket_WH") (pin "P13") (pinfunction "P13_P13") (pintype "passive"))
      (node (ref "MXM314-92p2x9p6-0p5-socket_WH") (pin "P131") (pinfunction "P131_P131") (pintype "passive"))
      (node (ref "MXM314-92p2x9p6-0p5-socket_WH") (pin "P134") (pinfunction "P134_P134") (pintype "passive"))
      (node (ref "MXM314-92p2x9p6-0p5-socket_WH") (pin "P137") (pinfunction "P137_P137") (pintype "passive"))
      (node (ref "MXM314-92p2x9p6-0p5-socket_WH") (pin "P14") (pinfunction "P14_P14") (pintype "passive"))
      (node (ref "MXM314-92p2x9p6-0p5-socket_WH") (pin "P140") (pinfunction "P140_P140") (pintype "passive"))
      (node (ref "MXM314-92p2x9p6-0p5-socket_WH") (pin "P151") (pinfunction "P151_P151") (pintype "passive"))
      (node (ref "MXM314-92p2x9p6-0p5-socket_WH") (pin "P152") (pinfunction "P152_P152") (pintype "passive"))
      (node (ref "MXM314-92p2x9p6-0p5-socket_WH") (pin "P153") (pinfunction "P153_P153") (pintype "passive"))
      (node (ref "MXM314-92p2x9p6-0p5-socket_WH") (pin "P154") (pinfunction "P154_P154") (pintype "passive"))
      (node (ref "MXM314-92p2x9p6-0p5-socket_WH") (pin "P155") (pinfunction "P155_P155") (pintype "passive"))
      (node (ref "MXM314-92p2x9p6-0p5-socket_WH") (pin "P156") (pinfunction "P156_P156") (pintype "passive"))
      (node (ref "MXM314-92p2x9p6-0p5-socket_WH") (pin "P17") (pinfunction "P17_P17") (pintype "passive"))
      (node (ref "MXM314-92p2x9p6-0p5-socket_WH") (pin "P2") (pinfunction "P2_P2") (pintype "passive"))
      (node (ref "MXM314-92p2x9p6-0p5-socket_WH") (pin "P20") (pinfunction "P20_P20") (pintype "passive"))
      (node (ref "MXM314-92p2x9p6-0p5-socket_WH") (pin "P23") (pinfunction "P23_P23") (pintype "passive"))
      (node (ref "MXM314-92p2x9p6-0p5-socket_WH") (pin "P26") (pinfunction "P26_P26") (pintype "passive"))
      (node (ref "MXM314-92p2x9p6-0p5-socket_WH") (pin "P29") (pinfunction "P29_P29") (pintype "passive"))
      (node (ref "MXM314-92p2x9p6-0p5-socket_WH") (pin "P3") (pinfunction "P3_P3") (pintype "passive"))
      (node (ref "MXM314-92p2x9p6-0p5-socket_WH") (pin "P59") (pinfunction "P59_P59") (pintype "passive"))
      (node (ref "MXM314-92p2x9p6-0p5-socket_WH") (pin "P68") (pinfunction "P68_P68") (pintype "passive"))
      (node (ref "MXM314-92p2x9p6-0p5-socket_WH") (pin "P75") (pinfunction "P75_P75") (pintype "passive"))
      (node (ref "MXM314-92p2x9p6-0p5-socket_WH") (pin "P93") (pinfunction "P93_P93") (pintype "passive"))
      (node (ref "MXM314-92p2x9p6-0p5-socket_WH") (pin "P96") (pinfunction "P96_P96") (pintype "passive"))
      (node (ref "MXM314-92p2x9p6-0p5-socket_WH") (pin "P99") (pinfunction "P99_P99") (pintype "passive"))
      (node (ref "MXM314-92p2x9p6-0p5-socket_WH") (pin "S1") (pinfunction "S1_S1") (pintype "passive"))
      (node (ref "MXM314-92p2x9p6-0p5-socket_WH") (pin "S115") (pinfunction "S115_S115") (pintype "passive"))
      (node (ref "MXM314-92p2x9p6-0p5-socket_WH") (pin "S127") (pinfunction "S127_S127") (pintype "passive"))
      (node (ref "MXM314-92p2x9p6-0p5-socket_WH") (pin "S133") (pinfunction "S133_S133") (pintype "passive"))
      (node (ref "MXM314-92p2x9p6-0p5-socket_WH") (pin "S136") (pinfunction "S136_S136") (pintype "passive"))
      (node (ref "MXM314-92p2x9p6-0p5-socket_WH") (pin "S139") (pinfunction "S139_S139") (pintype "passive"))
      (node (ref "MXM314-92p2x9p6-0p5-socket_WH") (pin "S142") (pinfunction "S142_S142") (pintype "passive"))
      (node (ref "MXM314-92p2x9p6-0p5-socket_WH") (pin "S145") (pinfunction "S145_S145") (pintype "passive"))
      (node (ref "MXM314-92p2x9p6-0p5-socket_WH") (pin "S148") (pinfunction "S148_S148") (pintype "passive"))
      (node (ref "MXM314-92p2x9p6-0p5-socket_WH") (pin "S15") (pinfunction "S15_S15") (pintype "passive"))
      (node (ref "MXM314-92p2x9p6-0p5-socket_WH") (pin "S16") (pinfunction "S16_S16") (pintype "passive"))
      (node (ref "MXM314-92p2x9p6-0p5-socket_WH") (pin "S19") (pinfunction "S19_S19") (pintype "passive"))
      (node (ref "MXM314-92p2x9p6-0p5-socket_WH") (pin "S2") (pinfunction "S2_S2") (pintype "passive"))
      (node (ref "MXM314-92p2x9p6-0p5-socket_WH") (pin "S22") (pinfunction "S22_S22") (pintype "passive"))
      (node (ref "MXM314-92p2x9p6-0p5-socket_WH") (pin "S25") (pinfunction "S25_S25") (pintype "passive"))
      (node (ref "MXM314-92p2x9p6-0p5-socket_WH") (pin "S28") (pinfunction "S28_S28") (pintype "passive"))
      (node (ref "MXM314-92p2x9p6-0p5-socket_WH") (pin "S31") (pinfunction "S31_S31") (pintype "passive"))
      (node (ref "MXM314-92p2x9p6-0p5-socket_WH") (pin "S33") (pinfunction "S33_S33") (pintype "passive"))
      (node (ref "MXM314-92p2x9p6-0p5-socket_WH") (pin "S36") (pinfunction "S36_S36") (pintype "passive"))
      (node (ref "MXM314-92p2x9p6-0p5-socket_WH") (pin "S39") (pinfunction "S39_S39") (pintype "passive"))
      (node (ref "MXM314-92p2x9p6-0p5-socket_WH") (pin "S42") (pinfunction "S42_S42") (pintype "passive"))
      (node (ref "MXM314-92p2x9p6-0p5-socket_WH") (pin "S45") (pinfunction "S45_S45") (pintype "passive"))
      (node (ref "MXM314-92p2x9p6-0p5-socket_WH") (pin "S48") (pinfunction "S48_S48") (pintype "passive"))
      (node (ref "MXM314-92p2x9p6-0p5-socket_WH") (pin "S76") (pinfunction "S76_S76") (pintype "passive"))
      (node (ref "MXM314-92p2x9p6-0p5-socket_WH") (pin "S79") (pinfunction "S79_S79") (pintype "passive"))
      (node (ref "R1") (pin "2") (pinfunction "2_2") (pintype "passive"))
      (node (ref "R126") (pin "2") (pinfunction "2_2") (pintype "passive"))
      (node (ref "R95") (pin "2") (pinfunction "2_2") (pintype "passive"))
      (node (ref "R96") (pin "2") (pinfunction "2_2") (pintype "passive"))
      (node (ref "R97") (pin "2") (pinfunction "2_2") (pintype "passive"))
    )
    (net (code "232") (name "Net-(C1-Pad1)") (class "Default")
      (node (ref "C1") (pin "1") (pinfunction "1_1") (pintype "passive"))
      (node (ref "H1") (pin "1") (pinfunction "1_1") (pintype "passive"))
      (node (ref "R1") (pin "1") (pinfunction "1_1") (pintype "passive"))
    )
    (net (code "233") (name "Net-(C73-Pad1)") (class "Default")
      (node (ref "C73") (pin "1") (pinfunction "1_1") (pintype "passive"))
      (node (ref "H5") (pin "1") (pinfunction "1_1") (pintype "passive"))
      (node (ref "R95") (pin "1") (pinfunction "1_1") (pintype "passive"))
    )
    (net (code "234") (name "Net-(C74-Pad1)") (class "Default")
      (node (ref "C74") (pin "1") (pinfunction "1_1") (pintype "passive"))
      (node (ref "H6") (pin "1") (pinfunction "1_1") (pintype "passive"))
      (node (ref "R96") (pin "1") (pinfunction "1_1") (pintype "passive"))
    )
    (net (code "235") (name "Net-(C75-Pad1)") (class "Default")
      (node (ref "C75") (pin "1") (pinfunction "1_1") (pintype "passive"))
      (node (ref "H2") (pin "1") (pinfunction "1_1") (pintype "passive"))
      (node (ref "R97") (pin "1") (pinfunction "1_1") (pintype "passive"))
    )
    (net (code "236") (name "Net-(C112-Pad1)") (class "Default")
      (node (ref "C112") (pin "1") (pinfunction "1_1") (pintype "passive"))
      (node (ref "H4") (pin "1") (pinfunction "1_1") (pintype "passive"))
      (node (ref "R126") (pin "1") (pinfunction "1_1") (pintype "passive"))
    )
    (net (code "237") (name "USB_H1_VBUS") (class "Default")
      (node (ref "MXM314-92p2x9p6-0p5-socket_WH") (pin "P104") (pinfunction "P104_P104") (pintype "passive"))
    )
    (net (code "238") (name "USB_OTG_VBUS") (class "Default")
      (node (ref "MXM314-92p2x9p6-0p5-socket_WH") (pin "P103") (pinfunction "P103_P103") (pintype "passive"))
    )
    (net (code "239") (name "unconnected-(MXM314-92p2x9p6-0p5-socket_WH-PadP121)") (class "Default")
      (node (ref "MXM314-92p2x9p6-0p5-socket_WH") (pin "P121") (pinfunction "P121_P121") (pintype "passive"))
    )
    (net (code "240") (name "unconnected-(MXM314-92p2x9p6-0p5-socket_WH-PadP122)") (class "Default")
      (node (ref "MXM314-92p2x9p6-0p5-socket_WH") (pin "P122") (pinfunction "P122_P122") (pintype "passive"))
    )
    (net (code "241") (name "unconnected-(MXM314-92p2x9p6-0p5-socket_WH-PadP123)") (class "Default")
      (node (ref "MXM314-92p2x9p6-0p5-socket_WH") (pin "P123") (pinfunction "P123_P123") (pintype "passive"))
    )
    (net (code "242") (name "unconnected-(MXM314-92p2x9p6-0p5-socket_WH-PadP125)") (class "Default")
      (node (ref "MXM314-92p2x9p6-0p5-socket_WH") (pin "P125") (pinfunction "P125_P125") (pintype "passive"))
    )
    (net (code "243") (name "unconnected-(MXM314-92p2x9p6-0p5-socket_WH-PadP127)") (class "Default")
      (node (ref "MXM314-92p2x9p6-0p5-socket_WH") (pin "P127") (pinfunction "P127_P127") (pintype "passive"))
    )
    (net (code "244") (name "unconnected-(MXM314-92p2x9p6-0p5-socket_WH-PadP128)") (class "Default")
      (node (ref "MXM314-92p2x9p6-0p5-socket_WH") (pin "P128") (pinfunction "P128_P128") (pintype "passive"))
    )
    (net (code "245") (name "unconnected-(MXM314-92p2x9p6-0p5-socket_WH-PadP130)") (class "Default")
      (node (ref "MXM314-92p2x9p6-0p5-socket_WH") (pin "P130") (pinfunction "P130_P130") (pintype "passive"))
    )
    (net (code "246") (name "unconnected-(MXM314-92p2x9p6-0p5-socket_WH-PadP132)") (class "Default")
      (node (ref "MXM314-92p2x9p6-0p5-socket_WH") (pin "P132") (pinfunction "P132_P132") (pintype "passive"))
    )
    (net (code "247") (name "unconnected-(MXM314-92p2x9p6-0p5-socket_WH-PadP133)") (class "Default")
      (node (ref "MXM314-92p2x9p6-0p5-socket_WH") (pin "P133") (pinfunction "P133_P133") (pintype "passive"))
    )
    (net (code "248") (name "unconnected-(MXM314-92p2x9p6-0p5-socket_WH-PadP135)") (class "Default")
      (node (ref "MXM314-92p2x9p6-0p5-socket_WH") (pin "P135") (pinfunction "P135_P135") (pintype "passive"))
    )
    (net (code "249") (name "unconnected-(MXM314-92p2x9p6-0p5-socket_WH-PadP136)") (class "Default")
      (node (ref "MXM314-92p2x9p6-0p5-socket_WH") (pin "P136") (pinfunction "P136_P136") (pintype "passive"))
    )
    (net (code "250") (name "unconnected-(MXM314-92p2x9p6-0p5-socket_WH-PadP138)") (class "Default")
      (node (ref "MXM314-92p2x9p6-0p5-socket_WH") (pin "P138") (pinfunction "P138_P138") (pintype "passive"))
    )
    (net (code "251") (name "unconnected-(MXM314-92p2x9p6-0p5-socket_WH-PadP139)") (class "Default")
      (node (ref "MXM314-92p2x9p6-0p5-socket_WH") (pin "P139") (pinfunction "P139_P139") (pintype "passive"))
    )
  )
)
